# MONITOR_final_rev01.net
KiCad netlist of a schematic drawn in EAGLE
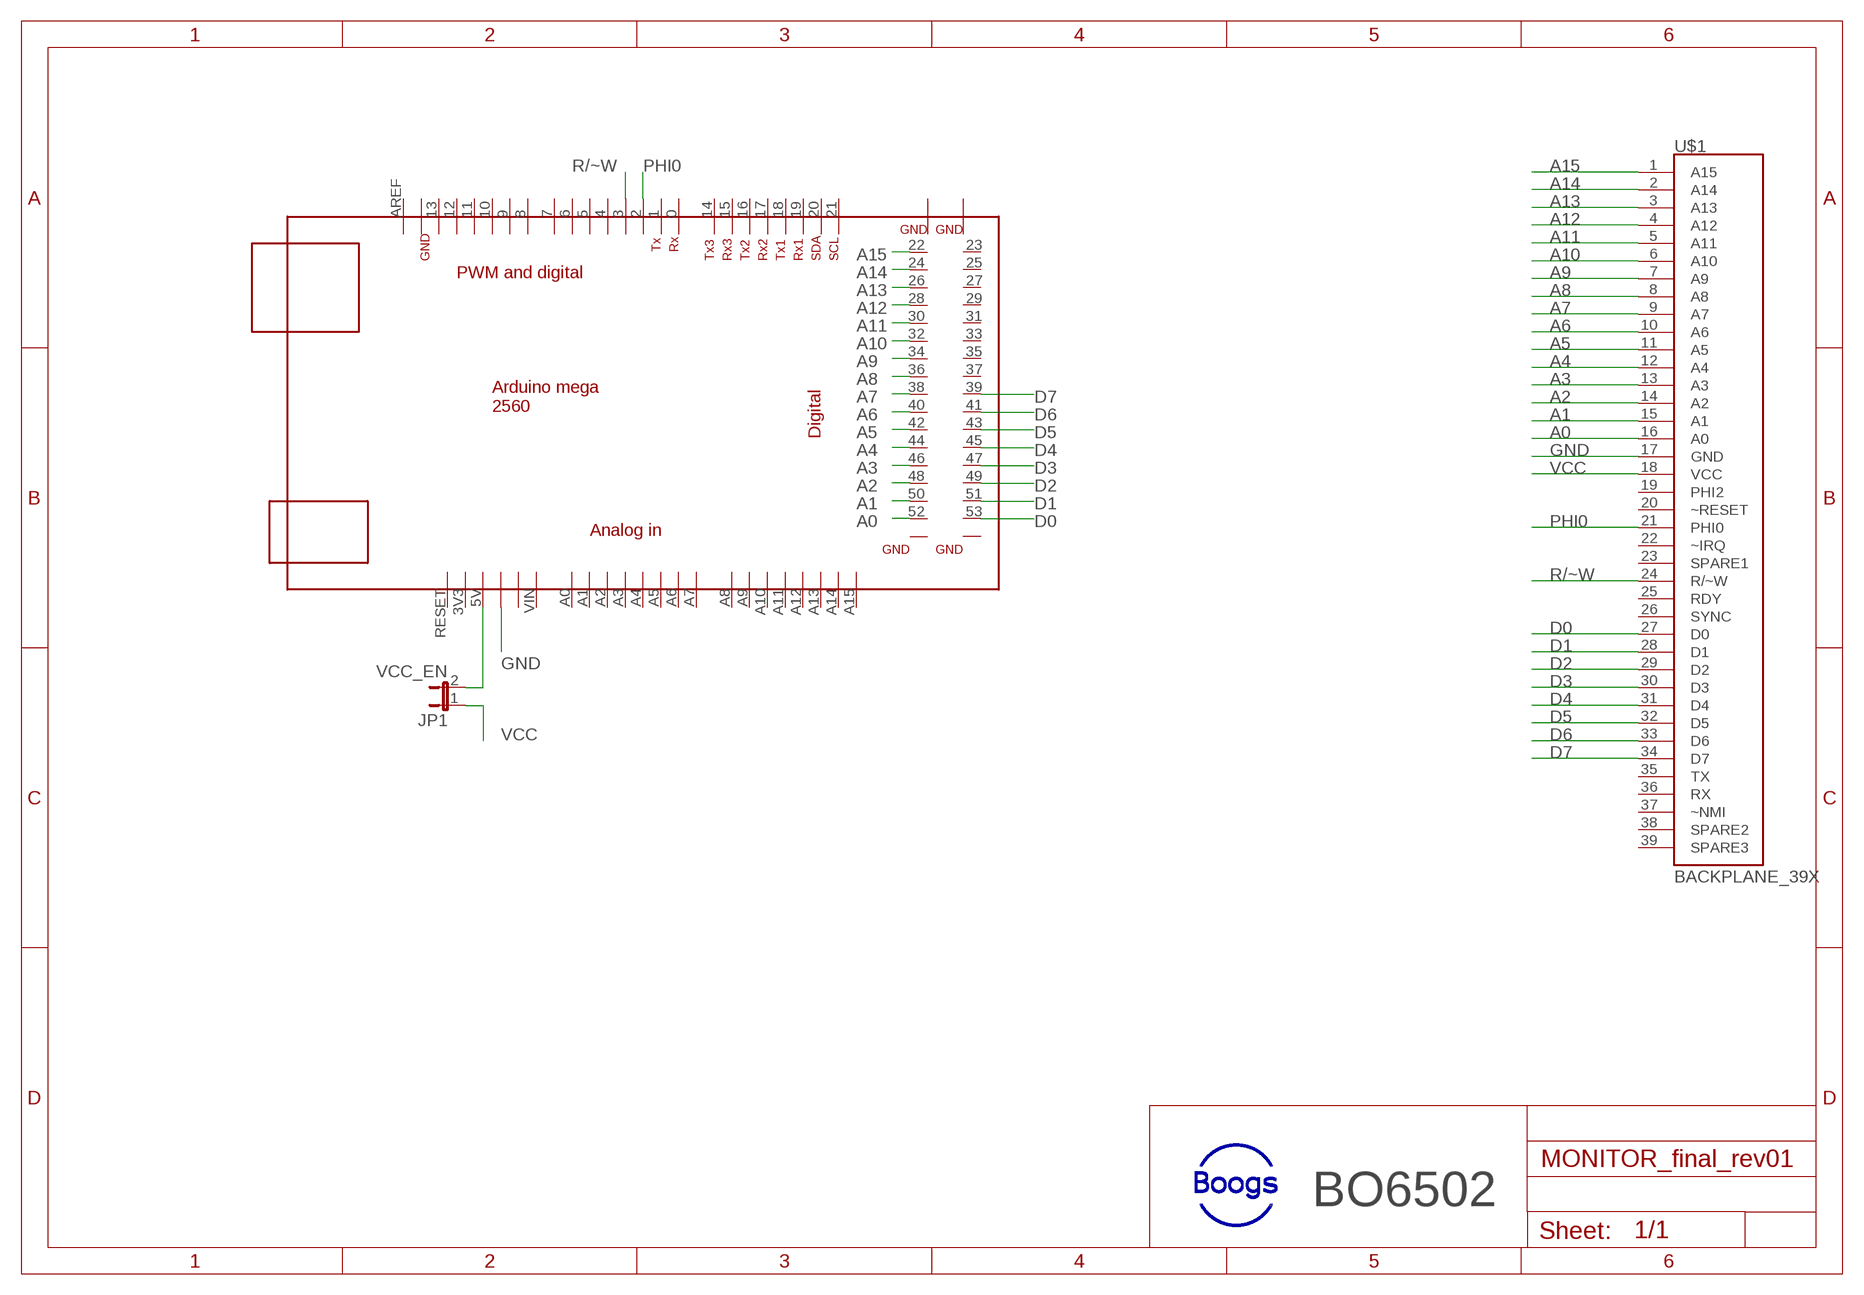
[diagram p0: schematic, sheet 1]

(export (version "E")
  (design (tool "Eeschema 10.0.6"))
  (components
    (comp (ref "JP1")
      (value "VCC_EN")
      (footprint "eagle-import:JP1")
      (libsource (lib "eagle-import") (part "JP1E"))
    )
    (comp (ref "U$1")
      (value "BACKPLANE_39X")
      (footprint "eagle-import:BP_39X")
      (fields (field (name "A15") "A15"))
      (libsource (lib "eagle-import") (part "BACKPLANE_39X"))
    )
    (comp (ref "U$2")
      (value "MEGA_DEVICE")
      (footprint "eagle-import:MEGAOUTLINE")
      (libsource (lib "eagle-import") (part "MEGA_DEVICE"))
    )
  )
  (nets
    (net (code "1") (name "/A0") (class "Default")
      (node (ref "U$1") (pin "16") (pinfunction "A0_16") (pintype "bidirectional"))
      (node (ref "U$2") (pin "52") (pinfunction "52_52") (pintype "bidirectional"))
    )
    (net (code "2") (name "/A1") (class "Default")
      (node (ref "U$1") (pin "15") (pinfunction "A1_15") (pintype "bidirectional"))
      (node (ref "U$2") (pin "50") (pinfunction "50_50") (pintype "bidirectional"))
    )
    (net (code "3") (name "/A2") (class "Default")
      (node (ref "U$1") (pin "14") (pinfunction "A2_14") (pintype "bidirectional"))
      (node (ref "U$2") (pin "48") (pinfunction "48_48") (pintype "bidirectional"))
    )
    (net (code "4") (name "/A3") (class "Default")
      (node (ref "U$1") (pin "13") (pinfunction "A3_13") (pintype "bidirectional"))
      (node (ref "U$2") (pin "46") (pinfunction "46_46") (pintype "bidirectional"))
    )
    (net (code "5") (name "/A4") (class "Default")
      (node (ref "U$1") (pin "12") (pinfunction "A4_12") (pintype "bidirectional"))
      (node (ref "U$2") (pin "44") (pinfunction "44_44") (pintype "bidirectional"))
    )
    (net (code "6") (name "/A5") (class "Default")
      (node (ref "U$1") (pin "11") (pinfunction "A5_11") (pintype "bidirectional"))
      (node (ref "U$2") (pin "42") (pinfunction "42_42") (pintype "bidirectional"))
    )
    (net (code "7") (name "/A6") (class "Default")
      (node (ref "U$1") (pin "10") (pinfunction "A6_10") (pintype "bidirectional"))
      (node (ref "U$2") (pin "40") (pinfunction "40_40") (pintype "bidirectional"))
    )
    (net (code "8") (name "/A7") (class "Default")
      (node (ref "U$1") (pin "9") (pinfunction "A7_9") (pintype "bidirectional"))
      (node (ref "U$2") (pin "38") (pinfunction "38_38") (pintype "bidirectional"))
    )
    (net (code "9") (name "/A8") (class "Default")
      (node (ref "U$1") (pin "8") (pinfunction "A8_8") (pintype "bidirectional"))
      (node (ref "U$2") (pin "36") (pinfunction "36_36") (pintype "bidirectional"))
    )
    (net (code "10") (name "/A9") (class "Default")
      (node (ref "U$1") (pin "7") (pinfunction "A9_7") (pintype "bidirectional"))
      (node (ref "U$2") (pin "34") (pinfunction "34_34") (pintype "bidirectional"))
    )
    (net (code "11") (name "/A10") (class "Default")
      (node (ref "U$1") (pin "6") (pinfunction "A10_6") (pintype "bidirectional"))
      (node (ref "U$2") (pin "32") (pinfunction "32_32") (pintype "bidirectional"))
    )
    (net (code "12") (name "/A11") (class "Default")
      (node (ref "U$1") (pin "5") (pinfunction "A11_5") (pintype "bidirectional"))
      (node (ref "U$2") (pin "30") (pinfunction "30_30") (pintype "bidirectional"))
    )
    (net (code "13") (name "/A12") (class "Default")
      (node (ref "U$1") (pin "4") (pinfunction "A12_4") (pintype "bidirectional"))
      (node (ref "U$2") (pin "28") (pinfunction "28_28") (pintype "bidirectional"))
    )
    (net (code "14") (name "/A13") (class "Default")
      (node (ref "U$1") (pin "3") (pinfunction "A13_3") (pintype "bidirectional"))
      (node (ref "U$2") (pin "26") (pinfunction "26_26") (pintype "bidirectional"))
    )
    (net (code "15") (name "/A14") (class "Default")
      (node (ref "U$1") (pin "2") (pinfunction "A14_2") (pintype "bidirectional"))
      (node (ref "U$2") (pin "24") (pinfunction "24_24") (pintype "bidirectional"))
    )
    (net (code "16") (name "/A15") (class "Default")
      (node (ref "U$1") (pin "1") (pinfunction "A15_1") (pintype "bidirectional"))
      (node (ref "U$2") (pin "22") (pinfunction "22_22") (pintype "bidirectional"))
    )
    (net (code "17") (name "/D0") (class "Default")
      (node (ref "U$1") (pin "27") (pinfunction "D0_27") (pintype "bidirectional"))
      (node (ref "U$2") (pin "53") (pinfunction "53_53") (pintype "bidirectional"))
    )
    (net (code "18") (name "/D1") (class "Default")
      (node (ref "U$1") (pin "28") (pinfunction "D1_28") (pintype "bidirectional"))
      (node (ref "U$2") (pin "51") (pinfunction "51_51") (pintype "bidirectional"))
    )
    (net (code "19") (name "/D2") (class "Default")
      (node (ref "U$1") (pin "29") (pinfunction "D2_29") (pintype "bidirectional"))
      (node (ref "U$2") (pin "49") (pinfunction "49_49") (pintype "bidirectional"))
    )
    (net (code "20") (name "/D3") (class "Default")
      (node (ref "U$1") (pin "30") (pinfunction "D3_30") (pintype "bidirectional"))
      (node (ref "U$2") (pin "47") (pinfunction "47_47") (pintype "bidirectional"))
    )
    (net (code "21") (name "/D4") (class "Default")
      (node (ref "U$1") (pin "31") (pinfunction "D4_31") (pintype "bidirectional"))
      (node (ref "U$2") (pin "45") (pinfunction "45_45") (pintype "bidirectional"))
    )
    (net (code "22") (name "/D5") (class "Default")
      (node (ref "U$1") (pin "32") (pinfunction "D5_32") (pintype "bidirectional"))
      (node (ref "U$2") (pin "43") (pinfunction "43_43") (pintype "bidirectional"))
    )
    (net (code "23") (name "/D6") (class "Default")
      (node (ref "U$1") (pin "33") (pinfunction "D6_33") (pintype "bidirectional"))
      (node (ref "U$2") (pin "41") (pinfunction "41_41") (pintype "bidirectional"))
    )
    (net (code "24") (name "/D7") (class "Default")
      (node (ref "U$1") (pin "34") (pinfunction "D7_34") (pintype "bidirectional"))
      (node (ref "U$2") (pin "39") (pinfunction "39_39") (pintype "bidirectional"))
    )
    (net (code "25") (name "/GND") (class "Default")
      (node (ref "U$1") (pin "17") (pinfunction "GND_17") (pintype "bidirectional"))
      (node (ref "U$2") (pin "GND@2") (pinfunction "GND_GND@2") (pintype "bidirectional"))
    )
    (net (code "26") (name "/PHI0") (class "Default")
      (node (ref "U$1") (pin "21") (pinfunction "PHI0_21") (pintype "bidirectional"))
      (node (ref "U$2") (pin "2") (pinfunction "2_2") (pintype "bidirectional"))
    )
    (net (code "27") (name "/R{slash}~{W}") (class "Default")
      (node (ref "U$1") (pin "24") (pinfunction "R/~{W}_24") (pintype "bidirectional"))
      (node (ref "U$2") (pin "3") (pinfunction "3_3") (pintype "bidirectional"))
    )
    (net (code "28") (name "/VCC") (class "Default")
      (node (ref "JP1") (pin "1") (pinfunction "1_1") (pintype "passive"))
      (node (ref "U$1") (pin "18") (pinfunction "VCC_18") (pintype "bidirectional"))
    )
    (net (code "29") (name "Net-(JP1-Pad2)") (class "Default")
      (node (ref "JP1") (pin "2") (pinfunction "2_2") (pintype "passive"))
      (node (ref "U$2") (pin "5V") (pinfunction "5V_5V") (pintype "bidirectional"))
    )
    (net (code "30") (name "unconnected-(U$1-PHI2-Pad19)") (class "Default")
      (node (ref "U$1") (pin "19") (pinfunction "PHI2_19") (pintype "bidirectional"))
    )
    (net (code "31") (name "unconnected-(U$1-RDY-Pad25)") (class "Default")
      (node (ref "U$1") (pin "25") (pinfunction "RDY_25") (pintype "bidirectional"))
    )
    (net (code "32") (name "unconnected-(U$1-RX-Pad36)") (class "Default")
      (node (ref "U$1") (pin "36") (pinfunction "RX_36") (pintype "bidirectional"))
    )
    (net (code "33") (name "unconnected-(U$1-SPARE1-Pad23)") (class "Default")
      (node (ref "U$1") (pin "23") (pinfunction "SPARE1_23") (pintype "bidirectional"))
    )
    (net (code "34") (name "unconnected-(U$1-SPARE2-Pad38)") (class "Default")
      (node (ref "U$1") (pin "38") (pinfunction "SPARE2_38") (pintype "bidirectional"))
    )
    (net (code "35") (name "unconnected-(U$1-SPARE3-Pad39)") (class "Default")
      (node (ref "U$1") (pin "39") (pinfunction "SPARE3_39") (pintype "bidirectional"))
    )
    (net (code "36") (name "unconnected-(U$1-SYNC-Pad26)") (class "Default")
      (node (ref "U$1") (pin "26") (pinfunction "SYNC_26") (pintype "bidirectional"))
    )
    (net (code "37") (name "unconnected-(U$1-TX-Pad35)") (class "Default")
      (node (ref "U$1") (pin "35") (pinfunction "TX_35") (pintype "bidirectional"))
    )
    (net (code "38") (name "unconnected-(U$1-~{IRQ}-Pad22)") (class "Default")
      (node (ref "U$1") (pin "22") (pinfunction "~{IRQ}_22") (pintype "bidirectional"))
    )
    (net (code "39") (name "unconnected-(U$1-~{NMI}-Pad37)") (class "Default")
      (node (ref "U$1") (pin "37") (pinfunction "~{NMI}_37") (pintype "bidirectional"))
    )
    (net (code "40") (name "unconnected-(U$1-~{RESET}-Pad20)") (class "Default")
      (node (ref "U$1") (pin "20") (pinfunction "~{RESET}_20") (pintype "bidirectional"))
    )
    (net (code "41") (name "unconnected-(U$2-GND-PadGND@1)") (class "Default")
      (node (ref "U$2") (pin "GND@1") (pinfunction "GND_GND@1") (pintype "bidirectional"))
    )
    (net (code "42") (name "unconnected-(U$2-GND-PadGND@3)") (class "Default")
      (node (ref "U$2") (pin "GND@3") (pinfunction "GND_GND@3") (pintype "bidirectional"))
    )
    (net (code "43") (name "unconnected-(U$2-GND-PadGND@4)") (class "Default")
      (node (ref "U$2") (pin "GND@4") (pinfunction "GND_GND@4") (pintype "bidirectional"))
    )
    (net (code "44") (name "unconnected-(U$2-GND-PadGND@5)") (class "Default")
      (node (ref "U$2") (pin "GND@5") (pinfunction "GND_GND@5") (pintype "bidirectional"))
    )
    (net (code "45") (name "unconnected-(U$2-GND-PadGND@6)") (class "Default")
      (node (ref "U$2") (pin "GND@6") (pinfunction "GND_GND@6") (pintype "bidirectional"))
    )
    (net (code "46") (name "unconnected-(U$2-GND-PadGND@7)") (class "Default")
      (node (ref "U$2") (pin "GND@7") (pinfunction "GND_GND@7") (pintype "bidirectional"))
    )
    (net (code "47") (name "unconnected-(U$2-Pad0)") (class "Default")
      (node (ref "U$2") (pin "0") (pinfunction "0_0") (pintype "bidirectional"))
    )
    (net (code "48") (name "unconnected-(U$2-Pad1)") (class "Default")
      (node (ref "U$2") (pin "1") (pinfunction "1_1") (pintype "bidirectional"))
    )
    (net (code "49") (name "unconnected-(U$2-Pad3V3)") (class "Default")
      (node (ref "U$2") (pin "3V3") (pinfunction "3V3_3V3") (pintype "bidirectional"))
    )
    (net (code "50") (name "unconnected-(U$2-Pad4)") (class "Default")
      (node (ref "U$2") (pin "4") (pinfunction "4_4") (pintype "bidirectional"))
    )
    (net (code "51") (name "unconnected-(U$2-Pad5)") (class "Default")
      (node (ref "U$2") (pin "5") (pinfunction "5_5") (pintype "bidirectional"))
    )
    (net (code "52") (name "unconnected-(U$2-Pad6)") (class "Default")
      (node (ref "U$2") (pin "6") (pinfunction "6_6") (pintype "bidirectional"))
    )
    (net (code "53") (name "unconnected-(U$2-Pad7)") (class "Default")
      (node (ref "U$2") (pin "7") (pinfunction "7_7") (pintype "bidirectional"))
    )
    (net (code "54") (name "unconnected-(U$2-Pad8)") (class "Default")
      (node (ref "U$2") (pin "8") (pinfunction "8_8") (pintype "bidirectional"))
    )
    (net (code "55") (name "unconnected-(U$2-Pad9)") (class "Default")
      (node (ref "U$2") (pin "9") (pinfunction "9_9") (pintype "bidirectional"))
    )
    (net (code "56") (name "unconnected-(U$2-Pad10)") (class "Default")
      (node (ref "U$2") (pin "10") (pinfunction "10_10") (pintype "bidirectional"))
    )
    (net (code "57") (name "unconnected-(U$2-Pad11)") (class "Default")
      (node (ref "U$2") (pin "11") (pinfunction "11_11") (pintype "bidirectional"))
    )
    (net (code "58") (name "unconnected-(U$2-Pad12)") (class "Default")
      (node (ref "U$2") (pin "12") (pinfunction "12_12") (pintype "bidirectional"))
    )
    (net (code "59") (name "unconnected-(U$2-Pad13)") (class "Default")
      (node (ref "U$2") (pin "13") (pinfunction "13_13") (pintype "bidirectional"))
    )
    (net (code "60") (name "unconnected-(U$2-Pad14)") (class "Default")
      (node (ref "U$2") (pin "14") (pinfunction "14_14") (pintype "bidirectional"))
    )
    (net (code "61") (name "unconnected-(U$2-Pad15)") (class "Default")
      (node (ref "U$2") (pin "15") (pinfunction "15_15") (pintype "bidirectional"))
    )
    (net (code "62") (name "unconnected-(U$2-Pad16)") (class "Default")
      (node (ref "U$2") (pin "16") (pinfunction "16_16") (pintype "bidirectional"))
    )
    (net (code "63") (name "unconnected-(U$2-Pad17)") (class "Default")
      (node (ref "U$2") (pin "17") (pinfunction "17_17") (pintype "bidirectional"))
    )
    (net (code "64") (name "unconnected-(U$2-Pad18)") (class "Default")
      (node (ref "U$2") (pin "18") (pinfunction "18_18") (pintype "bidirectional"))
    )
    (net (code "65") (name "unconnected-(U$2-Pad19)") (class "Default")
      (node (ref "U$2") (pin "19") (pinfunction "19_19") (pintype "bidirectional"))
    )
    (net (code "66") (name "unconnected-(U$2-Pad20)") (class "Default")
      (node (ref "U$2") (pin "20") (pinfunction "20_20") (pintype "bidirectional"))
    )
    (net (code "67") (name "unconnected-(U$2-Pad21)") (class "Default")
      (node (ref "U$2") (pin "21") (pinfunction "21_21") (pintype "bidirectional"))
    )
    (net (code "68") (name "unconnected-(U$2-Pad23)") (class "Default")
      (node (ref "U$2") (pin "23") (pinfunction "23_23") (pintype "bidirectional"))
    )
    (net (code "69") (name "unconnected-(U$2-Pad25)") (class "Default")
      (node (ref "U$2") (pin "25") (pinfunction "25_25") (pintype "bidirectional"))
    )
    (net (code "70") (name "unconnected-(U$2-Pad27)") (class "Default")
      (node (ref "U$2") (pin "27") (pinfunction "27_27") (pintype "bidirectional"))
    )
    (net (code "71") (name "unconnected-(U$2-Pad29)") (class "Default")
      (node (ref "U$2") (pin "29") (pinfunction "29_29") (pintype "bidirectional"))
    )
    (net (code "72") (name "unconnected-(U$2-Pad31)") (class "Default")
      (node (ref "U$2") (pin "31") (pinfunction "31_31") (pintype "bidirectional"))
    )
    (net (code "73") (name "unconnected-(U$2-Pad33)") (class "Default")
      (node (ref "U$2") (pin "33") (pinfunction "33_33") (pintype "bidirectional"))
    )
    (net (code "74") (name "unconnected-(U$2-Pad35)") (class "Default")
      (node (ref "U$2") (pin "35") (pinfunction "35_35") (pintype "bidirectional"))
    )
    (net (code "75") (name "unconnected-(U$2-Pad37)") (class "Default")
      (node (ref "U$2") (pin "37") (pinfunction "37_37") (pintype "bidirectional"))
    )
    (net (code "76") (name "unconnected-(U$2-PadA0)") (class "Default")
      (node (ref "U$2") (pin "A0") (pinfunction "A0_A0") (pintype "bidirectional"))
    )
    (net (code "77") (name "unconnected-(U$2-PadA1)") (class "Default")
      (node (ref "U$2") (pin "A1") (pinfunction "A1_A1") (pintype "bidirectional"))
    )
    (net (code "78") (name "unconnected-(U$2-PadA2)") (class "Default")
      (node (ref "U$2") (pin "A2") (pinfunction "A2_A2") (pintype "bidirectional"))
    )
    (net (code "79") (name "unconnected-(U$2-PadA3)") (class "Default")
      (node (ref "U$2") (pin "A3") (pinfunction "A3_A3") (pintype "bidirectional"))
    )
    (net (code "80") (name "unconnected-(U$2-PadA4)") (class "Default")
      (node (ref "U$2") (pin "A4") (pinfunction "A4_A4") (pintype "bidirectional"))
    )
    (net (code "81") (name "unconnected-(U$2-PadA5)") (class "Default")
      (node (ref "U$2") (pin "A5") (pinfunction "A5_A5") (pintype "bidirectional"))
    )
    (net (code "82") (name "unconnected-(U$2-PadA6)") (class "Default")
      (node (ref "U$2") (pin "A6") (pinfunction "A6_A6") (pintype "bidirectional"))
    )
    (net (code "83") (name "unconnected-(U$2-PadA7)") (class "Default")
      (node (ref "U$2") (pin "A7") (pinfunction "A7_A7") (pintype "bidirectional"))
    )
    (net (code "84") (name "unconnected-(U$2-PadA8)") (class "Default")
      (node (ref "U$2") (pin "A8") (pinfunction "A8_A8") (pintype "bidirectional"))
    )
    (net (code "85") (name "unconnected-(U$2-PadA9)") (class "Default")
      (node (ref "U$2") (pin "A9") (pinfunction "A9_A9") (pintype "bidirectional"))
    )
    (net (code "86") (name "unconnected-(U$2-PadA10)") (class "Default")
      (node (ref "U$2") (pin "A10") (pinfunction "A10_A10") (pintype "bidirectional"))
    )
    (net (code "87") (name "unconnected-(U$2-PadA11)") (class "Default")
      (node (ref "U$2") (pin "A11") (pinfunction "A11_A11") (pintype "bidirectional"))
    )
    (net (code "88") (name "unconnected-(U$2-PadA12)") (class "Default")
      (node (ref "U$2") (pin "A12") (pinfunction "A12_A12") (pintype "bidirectional"))
    )
    (net (code "89") (name "unconnected-(U$2-PadA13)") (class "Default")
      (node (ref "U$2") (pin "A13") (pinfunction "A13_A13") (pintype "bidirectional"))
    )
    (net (code "90") (name "unconnected-(U$2-PadA14)") (class "Default")
      (node (ref "U$2") (pin "A14") (pinfunction "A14_A14") (pintype "bidirectional"))
    )
    (net (code "91") (name "unconnected-(U$2-PadA15)") (class "Default")
      (node (ref "U$2") (pin "A15") (pinfunction "A15_A15") (pintype "bidirectional"))
    )
    (net (code "92") (name "unconnected-(U$2-PadAREF)") (class "Default")
      (node (ref "U$2") (pin "AREF") (pinfunction "AREF_AREF") (pintype "bidirectional"))
    )
    (net (code "93") (name "unconnected-(U$2-PadRESET)") (class "Default")
      (node (ref "U$2") (pin "RESET") (pinfunction "RESET_RESET") (pintype "bidirectional"))
    )
    (net (code "94") (name "unconnected-(U$2-PadVIN)") (class "Default")
      (node (ref "U$2") (pin "VIN") (pinfunction "VIN_VIN") (pintype "bidirectional"))
    )
  )
)
